# JST_CONNECTOR_v4.net
KiCad netlist of a schematic drawn in EAGLE
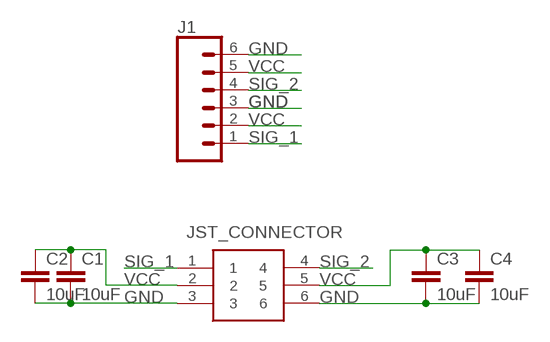
[diagram p0: schematic, sheet 1]

(export (version "E")
  (design (tool "Eeschema 10.0.6"))
  (components
    (comp (ref "C1")
      (value "10uF")
      (footprint "eagle-import:0805")
      (libsource (lib "eagle-import") (part "10UF-0805-10V-10%"))
    )
    (comp (ref "C2")
      (value "10uF")
      (footprint "eagle-import:0805")
      (libsource (lib "eagle-import") (part "10UF-0805-10V-10%"))
    )
    (comp (ref "C3")
      (value "10uF")
      (footprint "eagle-import:0805")
      (libsource (lib "eagle-import") (part "10UF-0805-10V-10%"))
    )
    (comp (ref "C4")
      (value "10uF")
      (footprint "eagle-import:0805")
      (libsource (lib "eagle-import") (part "10UF-0805-10V-10%"))
    )
    (comp (ref "J1")
      (value "CONN_06SILK_FEMALE_PTH")
      (footprint "eagle-import:1X06")
      (libsource (lib "eagle-import") (part "CONN_06SILK_FEMALE_PTH"))
    )
    (comp (ref "JST_CONNECTOR")
      (value "0532610671")
      (footprint "eagle-import:0532610671")
      (libsource (lib "eagle-import") (part "0532610671"))
    )
  )
  (nets
    (net (code "1") (name "/GND") (class "Default")
      (node (ref "C1") (pin "2") (pinfunction "2_2") (pintype "passive"))
      (node (ref "C2") (pin "2") (pinfunction "2_2") (pintype "passive"))
      (node (ref "C3") (pin "2") (pinfunction "2_2") (pintype "passive"))
      (node (ref "C4") (pin "2") (pinfunction "2_2") (pintype "passive"))
      (node (ref "J1") (pin "3") (pinfunction "3_3") (pintype "passive"))
      (node (ref "J1") (pin "6") (pinfunction "6_6") (pintype "passive"))
      (node (ref "JST_CONNECTOR") (pin "3") (pinfunction "3_3") (pintype "bidirectional"))
      (node (ref "JST_CONNECTOR") (pin "6") (pinfunction "6_6") (pintype "bidirectional"))
    )
    (net (code "2") (name "/SIG_1") (class "Default")
      (node (ref "J1") (pin "1") (pinfunction "1_1") (pintype "passive"))
      (node (ref "JST_CONNECTOR") (pin "1") (pinfunction "1_1") (pintype "bidirectional"))
    )
    (net (code "3") (name "/SIG_2") (class "Default")
      (node (ref "J1") (pin "4") (pinfunction "4_4") (pintype "passive"))
      (node (ref "JST_CONNECTOR") (pin "4") (pinfunction "4_4") (pintype "bidirectional"))
    )
    (net (code "4") (name "/VCC") (class "Default")
      (node (ref "C1") (pin "1") (pinfunction "1_1") (pintype "passive"))
      (node (ref "C2") (pin "1") (pinfunction "1_1") (pintype "passive"))
      (node (ref "C3") (pin "1") (pinfunction "1_1") (pintype "passive"))
      (node (ref "C4") (pin "1") (pinfunction "1_1") (pintype "passive"))
      (node (ref "J1") (pin "2") (pinfunction "2_2") (pintype "passive"))
      (node (ref "J1") (pin "5") (pinfunction "5_5") (pintype "passive"))
      (node (ref "JST_CONNECTOR") (pin "2") (pinfunction "2_2") (pintype "bidirectional"))
      (node (ref "JST_CONNECTOR") (pin "5") (pinfunction "5_5") (pintype "bidirectional"))
    )
  )
)
